# SalidasDigitales.net
KiCad netlist of a schematic drawn in Altium Designer
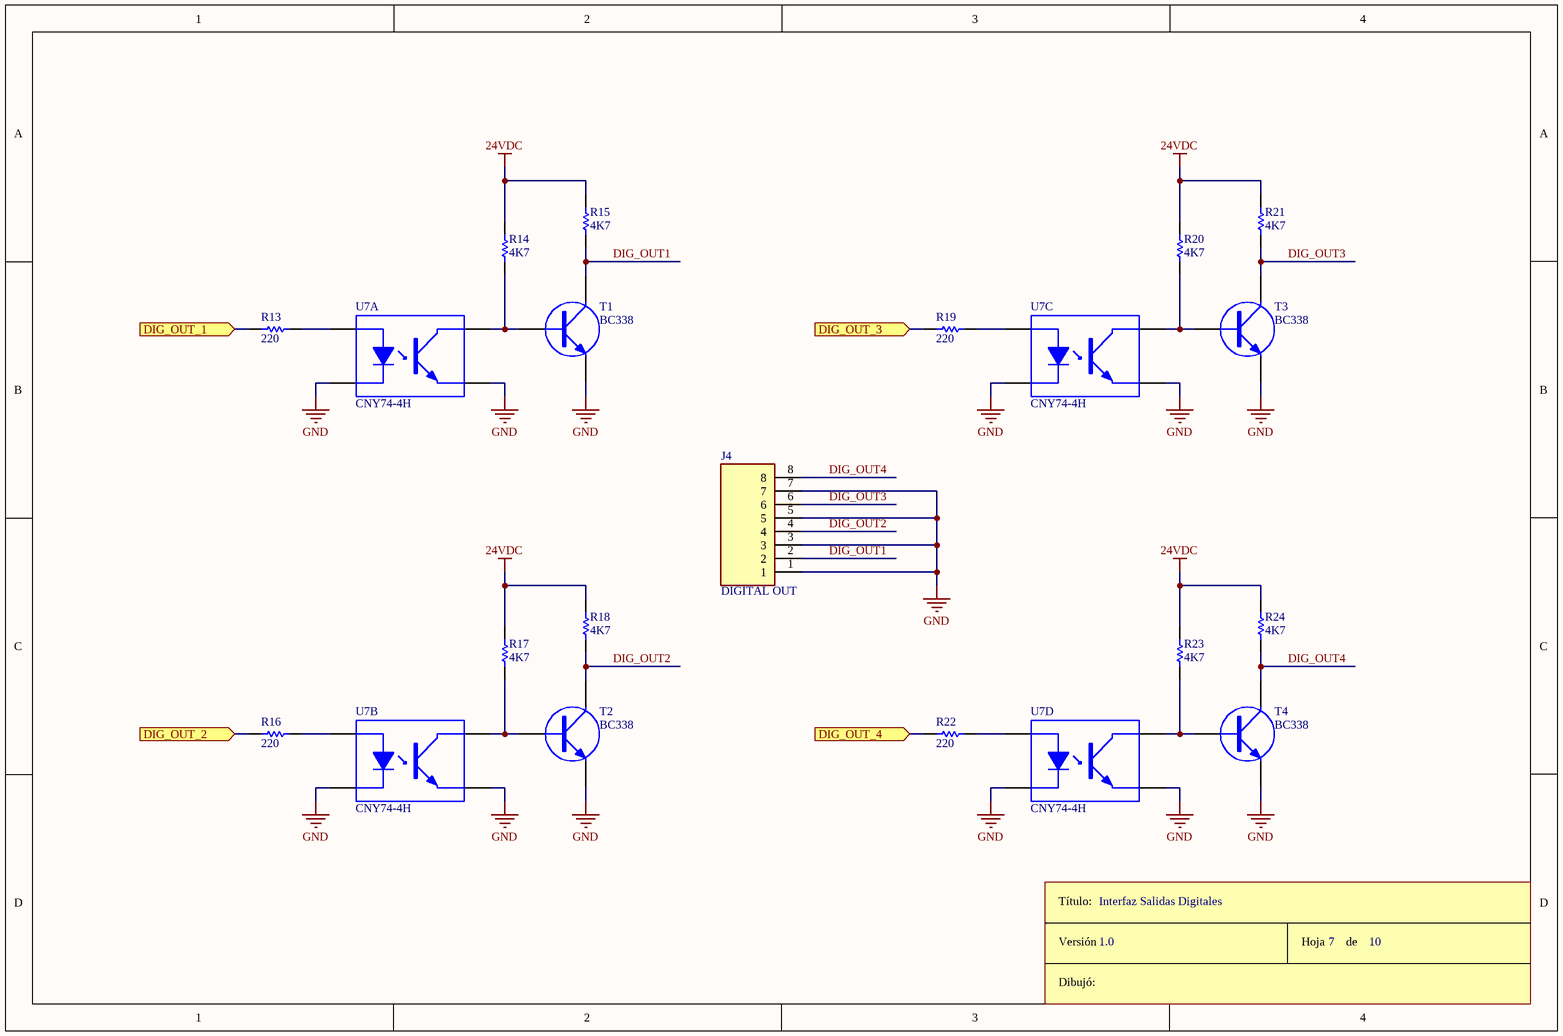
[diagram p0: SalidasDigitales.SchDoc]

(export (version "E")
  (design (tool "Eeschema 10.0.6"))
  (components
    (comp (ref "J4")
      (value "DIGITAL OUT")
      (footprint "TE_1586863-8")
      (description "Conn Power HDR 8 POS 4.2mm Solder RA Thru-Hole 8 Terminal 1 Port Tray")
      (fields (field (name "MF") "TE Connectivity") (field (name "MP") "1586863-8"))
      (libsource (lib "MFW8R") (part "1586863-8"))
    )
    (comp (ref "R13") (value "220") (footprint "RES400") (libsource (lib "LIBEBAL") (part "RES")))
    (comp (ref "R14") (value "4K7") (footprint "RES400") (libsource (lib "LIBEBAL") (part "RES")))
    (comp (ref "R15") (value "4K7") (footprint "RES400") (libsource (lib "LIBEBAL") (part "RES")))
    (comp (ref "R16") (value "220") (footprint "RES400") (libsource (lib "LIBEBAL") (part "RES")))
    (comp (ref "R17") (value "4K7") (footprint "RES400") (libsource (lib "LIBEBAL") (part "RES")))
    (comp (ref "R18") (value "4K7") (footprint "RES400") (libsource (lib "LIBEBAL") (part "RES")))
    (comp (ref "R19") (value "220") (footprint "RES400") (libsource (lib "LIBEBAL") (part "RES")))
    (comp (ref "R20") (value "4K7") (footprint "RES400") (libsource (lib "LIBEBAL") (part "RES")))
    (comp (ref "R21") (value "4K7") (footprint "RES400") (libsource (lib "LIBEBAL") (part "RES")))
    (comp (ref "R22") (value "220") (footprint "RES400") (libsource (lib "LIBEBAL") (part "RES")))
    (comp (ref "R23") (value "4K7") (footprint "RES400") (libsource (lib "LIBEBAL") (part "RES")))
    (comp (ref "R24") (value "4K7") (footprint "RES400") (libsource (lib "LIBEBAL") (part "RES")))
    (comp (ref "ROT6") (value "Rótulo") (libsource (lib "LIB PIO IX") (part "Rótulo")))
    (comp (ref "T1") (value "BC338") (footprint "TO92") (libsource (lib "LIBEBAL") (part "TRANSISTOR NPN")))
    (comp (ref "T2") (value "BC338") (footprint "TO92") (libsource (lib "LIBEBAL") (part "TRANSISTOR NPN")))
    (comp (ref "T3") (value "BC338") (footprint "TO92") (libsource (lib "LIBEBAL") (part "TRANSISTOR NPN")))
    (comp (ref "T4") (value "BC338") (footprint "TO92") (libsource (lib "LIBEBAL") (part "TRANSISTOR NPN")))
    (comp (ref "U7") (value "CNY74-4H") (footprint "DIP16") (libsource (lib "LIBEBAL") (part "CNY74-4H")))
  )
  (nets
    (net (code "1") (name "/DIG_OUT1") (class "Default")
      (node (ref "J4") (pin "2") (pinfunction "2_2") (pintype "passive"))
      (node (ref "R15") (pin "1") (pinfunction "1_1") (pintype "passive"))
      (node (ref "T1") (pin "2") (pinfunction "C_2") (pintype "passive"))
    )
    (net (code "2") (name "/DIG_OUT2") (class "Default")
      (node (ref "J4") (pin "4") (pinfunction "4_4") (pintype "passive"))
      (node (ref "R18") (pin "1") (pinfunction "1_1") (pintype "passive"))
      (node (ref "T2") (pin "2") (pinfunction "C_2") (pintype "passive"))
    )
    (net (code "3") (name "/DIG_OUT3") (class "Default")
      (node (ref "J4") (pin "6") (pinfunction "6_6") (pintype "passive"))
      (node (ref "R21") (pin "1") (pinfunction "1_1") (pintype "passive"))
      (node (ref "T3") (pin "2") (pinfunction "C_2") (pintype "passive"))
    )
    (net (code "4") (name "/DIG_OUT4") (class "Default")
      (node (ref "J4") (pin "8") (pinfunction "8_8") (pintype "passive"))
      (node (ref "R24") (pin "1") (pinfunction "1_1") (pintype "passive"))
      (node (ref "T4") (pin "2") (pinfunction "C_2") (pintype "passive"))
    )
    (net (code "5") (name "/DIG_OUT_1") (class "Default")
      (node (ref "R13") (pin "1") (pinfunction "1_1") (pintype "passive"))
    )
    (net (code "6") (name "/DIG_OUT_2") (class "Default")
      (node (ref "R16") (pin "1") (pinfunction "1_1") (pintype "passive"))
    )
    (net (code "7") (name "/DIG_OUT_3") (class "Default")
      (node (ref "R19") (pin "1") (pinfunction "1_1") (pintype "passive"))
    )
    (net (code "8") (name "/DIG_OUT_4") (class "Default")
      (node (ref "R22") (pin "1") (pinfunction "1_1") (pintype "passive"))
    )
    (net (code "9") (name "24VDC") (class "Default")
      (node (ref "R14") (pin "2") (pinfunction "2_2") (pintype "passive"))
      (node (ref "R15") (pin "2") (pinfunction "2_2") (pintype "passive"))
      (node (ref "R17") (pin "2") (pinfunction "2_2") (pintype "passive"))
      (node (ref "R18") (pin "2") (pinfunction "2_2") (pintype "passive"))
      (node (ref "R20") (pin "2") (pinfunction "2_2") (pintype "passive"))
      (node (ref "R21") (pin "2") (pinfunction "2_2") (pintype "passive"))
      (node (ref "R23") (pin "2") (pinfunction "2_2") (pintype "passive"))
      (node (ref "R24") (pin "2") (pinfunction "2_2") (pintype "passive"))
    )
    (net (code "10") (name "GND") (class "Default")
      (node (ref "J4") (pin "1") (pinfunction "1_1") (pintype "passive"))
      (node (ref "J4") (pin "3") (pinfunction "3_3") (pintype "passive"))
      (node (ref "J4") (pin "5") (pinfunction "5_5") (pintype "passive"))
      (node (ref "J4") (pin "7") (pinfunction "7_7") (pintype "passive"))
      (node (ref "T1") (pin "3") (pinfunction "E_3") (pintype "passive"))
      (node (ref "T2") (pin "3") (pinfunction "E_3") (pintype "passive"))
      (node (ref "T3") (pin "3") (pinfunction "E_3") (pintype "passive"))
      (node (ref "T4") (pin "3") (pinfunction "E_3") (pintype "passive"))
      (node (ref "U7") (pin "12") (pinfunction "E_12") (pintype "passive"))
      (node (ref "U7") (pin "13") (pinfunction "E_13") (pintype "passive"))
      (node (ref "U7") (pin "16") (pinfunction "E_16") (pintype "passive"))
      (node (ref "U7") (pin "2") (pinfunction "K_2") (pintype "passive"))
      (node (ref "U7") (pin "3") (pinfunction "K_3") (pintype "passive"))
      (node (ref "U7") (pin "6") (pinfunction "K_6") (pintype "passive"))
      (node (ref "U7") (pin "7") (pinfunction "K_7") (pintype "passive"))
      (node (ref "U7") (pin "9") (pinfunction "E_9") (pintype "passive"))
    )
    (net (code "11") (name "Net-(T1-B)") (class "Default")
      (node (ref "R14") (pin "1") (pinfunction "1_1") (pintype "passive"))
      (node (ref "T1") (pin "1") (pinfunction "B_1") (pintype "passive"))
      (node (ref "U7") (pin "15") (pinfunction "C_15") (pintype "passive"))
    )
    (net (code "12") (name "Net-(T2-B)") (class "Default")
      (node (ref "R17") (pin "1") (pinfunction "1_1") (pintype "passive"))
      (node (ref "T2") (pin "1") (pinfunction "B_1") (pintype "passive"))
      (node (ref "U7") (pin "14") (pinfunction "C_14") (pintype "passive"))
    )
    (net (code "13") (name "Net-(T3-B)") (class "Default")
      (node (ref "R20") (pin "1") (pinfunction "1_1") (pintype "passive"))
      (node (ref "T3") (pin "1") (pinfunction "B_1") (pintype "passive"))
      (node (ref "U7") (pin "11") (pinfunction "C_11") (pintype "passive"))
    )
    (net (code "14") (name "Net-(T4-B)") (class "Default")
      (node (ref "R23") (pin "1") (pinfunction "1_1") (pintype "passive"))
      (node (ref "T4") (pin "1") (pinfunction "B_1") (pintype "passive"))
      (node (ref "U7") (pin "10") (pinfunction "C_10") (pintype "passive"))
    )
    (net (code "15") (name "Net-(U7A-A)") (class "Default")
      (node (ref "R13") (pin "2") (pinfunction "2_2") (pintype "passive"))
      (node (ref "U7") (pin "1") (pinfunction "A_1") (pintype "passive"))
    )
    (net (code "16") (name "Net-(U7B-A)") (class "Default")
      (node (ref "R16") (pin "2") (pinfunction "2_2") (pintype "passive"))
      (node (ref "U7") (pin "4") (pinfunction "A_4") (pintype "passive"))
    )
    (net (code "17") (name "Net-(U7C-A)") (class "Default")
      (node (ref "R19") (pin "2") (pinfunction "2_2") (pintype "passive"))
      (node (ref "U7") (pin "5") (pinfunction "A_5") (pintype "passive"))
    )
    (net (code "18") (name "Net-(U7D-A)") (class "Default")
      (node (ref "R22") (pin "2") (pinfunction "2_2") (pintype "passive"))
      (node (ref "U7") (pin "8") (pinfunction "A_8") (pintype "passive"))
    )
  )
)
